# LM317AdjReg.net
KiCad netlist of a schematic drawn in Altium Designer
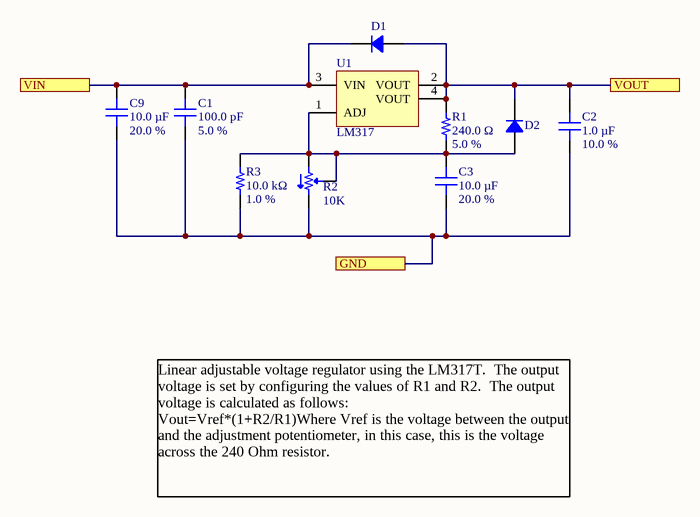
[diagram p0: LM317AdjReg.SchDoc]

(export (version "E")
  (design (tool "Eeschema 10.0.6"))
  (components
    (comp (ref "C1")
      (value "100.0 pF")
      (footprint "PCB - CAPACITOR - MLCC - CAP 0603_1608")
      (description "100 pF ±5% 50V Ceramic Capacitor X7R 0603 (1608 Metric)")
      (fields
        (field (name "ROWAN PART NUMBER") "1535")
        (field (name "TOLERANCE") "5.0 %")
        (field (name "MANUFACTURER") "YAGEO")
      )
      (libsource (lib "RowanAltiumLibrary") (part "SCH - PASSIVES - CAPACITOR"))
    )
    (comp (ref "C2")
      (value "1.0 µF")
      (footprint "PCB - CAPACITOR - MLCC - CAP 0603_1608")
      (description "1 µF ±10% 25V Ceramic Capacitor X7R 0603 (1608 Metric)")
      (fields
        (field (name "ROWAN PART NUMBER") "1552")
        (field (name "TOLERANCE") "10.0 %")
        (field (name "MANUFACTURER") "YAGEO")
      )
      (libsource (lib "RowanAltiumLibrary") (part "SCH - PASSIVES - CAPACITOR"))
    )
    (comp (ref "C3")
      (value "10.0 µF")
      (footprint "PCB - CAPACITOR - MLCC - CAP 0603_1608")
      (description "10 µF ±20% 16V Ceramic Capacitor X5R 0603 (1608 Metric)")
      (fields
        (field (name "ROWAN PART NUMBER") "1572")
        (field (name "TOLERANCE") "20.0 %")
        (field (name "MANUFACTURER") "YAGEO")
      )
      (libsource (lib "RowanAltiumLibrary") (part "SCH - PASSIVES - CAPACITOR"))
    )
    (comp (ref "C9")
      (value "10.0 µF")
      (footprint "PCB - CAPACITOR - MLCC - CAP 0603_1608")
      (description "10 µF ±20% 16V Ceramic Capacitor X5R 0603 (1608 Metric)")
      (fields
        (field (name "ROWAN PART NUMBER") "1572")
        (field (name "TOLERANCE") "20.0 %")
        (field (name "MANUFACTURER") "YAGEO")
      )
      (libsource (lib "RowanAltiumLibrary") (part "SCH - PASSIVES - CAPACITOR"))
    )
    (comp (ref "D1")
      (value "CDSU4148")
      (footprint "PCB - DIODES - SOD523F")
      (description "Diode Standard 75 V 150mA Surface Mount 0603/SOD-523F")
      (fields (field (name "ROWAN PART NUMBER") "1611") (field (name "MANUFACTURER") "Comchip Technology"))
      (libsource (lib "RowanAltiumLibrary") (part "SCH - DIODES - DIODE"))
    )
    (comp (ref "D2")
      (value "CDSU4148")
      (footprint "PCB - DIODES - SOD523F")
      (description "Diode Standard 75 V 150mA Surface Mount 0603/SOD-523F")
      (fields (field (name "ROWAN PART NUMBER") "1611") (field (name "MANUFACTURER") "Comchip Technology"))
      (libsource (lib "RowanAltiumLibrary") (part "SCH - DIODES - DIODE"))
    )
    (comp (ref "R1")
      (value "240.0 Ω")
      (footprint "PCB - RESISTOR - AXIAL")
      (description "240 Ohms ±5% 0.25W, 1/4W Through Hole Resistor Axial  Carbon Film")
      (fields
        (field (name "ROWAN PART NUMBER") "57")
        (field (name "TOLERANCE") "5.0 %")
        (field (name "MANUFACTURER") "Yageo")
      )
      (libsource (lib "RowanAltiumLibrary") (part "SCH - PASSIVES - RESISTOR"))
    )
    (comp (ref "R2")
      (value "10K")
      (footprint "TrimmerPot")
      (description "Potentiometer")
      (fields (field (name "ROWAN PART NUMBER") "1349"))
      (libsource (lib "ECE Modules") (part "Potentiometer"))
    )
    (comp (ref "R3")
      (value "10.0 kΩ")
      (footprint "PCB - RESISTOR - CHIP - RES 0603_1608")
      (description "10 kOhms ±1% 0.1W, 1/10W Chip Resistor 0603 (1608 Metric) Moisture Resistant Thick Film")
      (fields
        (field (name "ROWAN PART NUMBER") "1416")
        (field (name "TOLERANCE") "1.0 %")
        (field (name "MANUFACTURER") "Yageo")
      )
      (libsource (lib "RowanAltiumLibrary") (part "SCH - PASSIVES - RESISTOR"))
    )
    (comp (ref "U1")
      (value "LM317")
      (footprint "PCB - LEADED - SOT - SOT-223")
      (description "Linear Voltage Regulator IC Positive Adjustable 1 Output 1.5A SOT-223-4")
      (fields (field (name "ROWAN PART NUMBER") "1613") (field (name "MANUFACTURER") "Texas Instruments"))
      (libsource (lib "RowanAltiumLibrary") (part "SCH - POWER - LINEAR VREG - TI LM317-N"))
    )
  )
  (nets
    (net (code "1") (name "/GND") (class "Default")
      (node (ref "C1") (pin "1") (pinfunction "1_1") (pintype "passive"))
      (node (ref "C2") (pin "1") (pinfunction "1_1") (pintype "passive"))
      (node (ref "C3") (pin "1") (pinfunction "1_1") (pintype "passive"))
      (node (ref "C9") (pin "1") (pinfunction "1_1") (pintype "passive"))
      (node (ref "R2") (pin "3") (pinfunction "3_3") (pintype "passive"))
      (node (ref "R3") (pin "1") (pinfunction "1_1") (pintype "passive"))
    )
    (net (code "2") (name "/VIN") (class "Default")
      (node (ref "C1") (pin "2") (pinfunction "2_2") (pintype "passive"))
      (node (ref "C9") (pin "2") (pinfunction "2_2") (pintype "passive"))
      (node (ref "D1") (pin "2") (pinfunction "2_2") (pintype "passive"))
      (node (ref "U1") (pin "3") (pinfunction "VIN_3") (pintype "passive"))
    )
    (net (code "3") (name "/VOUT") (class "Default")
      (node (ref "C2") (pin "2") (pinfunction "2_2") (pintype "passive"))
      (node (ref "D1") (pin "1") (pinfunction "1_1") (pintype "passive"))
      (node (ref "D2") (pin "2") (pinfunction "2_2") (pintype "passive"))
      (node (ref "R1") (pin "2") (pinfunction "2_2") (pintype "passive"))
      (node (ref "U1") (pin "2") (pinfunction "VOUT_2") (pintype "passive"))
      (node (ref "U1") (pin "4") (pinfunction "VOUT_4") (pintype "passive"))
    )
    (net (code "4") (name "Net-(U1-ADJ)") (class "Default")
      (node (ref "C3") (pin "2") (pinfunction "2_2") (pintype "passive"))
      (node (ref "D2") (pin "1") (pinfunction "1_1") (pintype "passive"))
      (node (ref "R1") (pin "1") (pinfunction "1_1") (pintype "passive"))
      (node (ref "R2") (pin "1") (pinfunction "1_1") (pintype "passive"))
      (node (ref "R2") (pin "2") (pinfunction "2_2") (pintype "passive"))
      (node (ref "R3") (pin "2") (pinfunction "2_2") (pintype "passive"))
      (node (ref "U1") (pin "1") (pinfunction "ADJ_1") (pintype "passive"))
    )
  )
)
